# Overview.net
KiCad netlist of a schematic drawn in Altium Designer
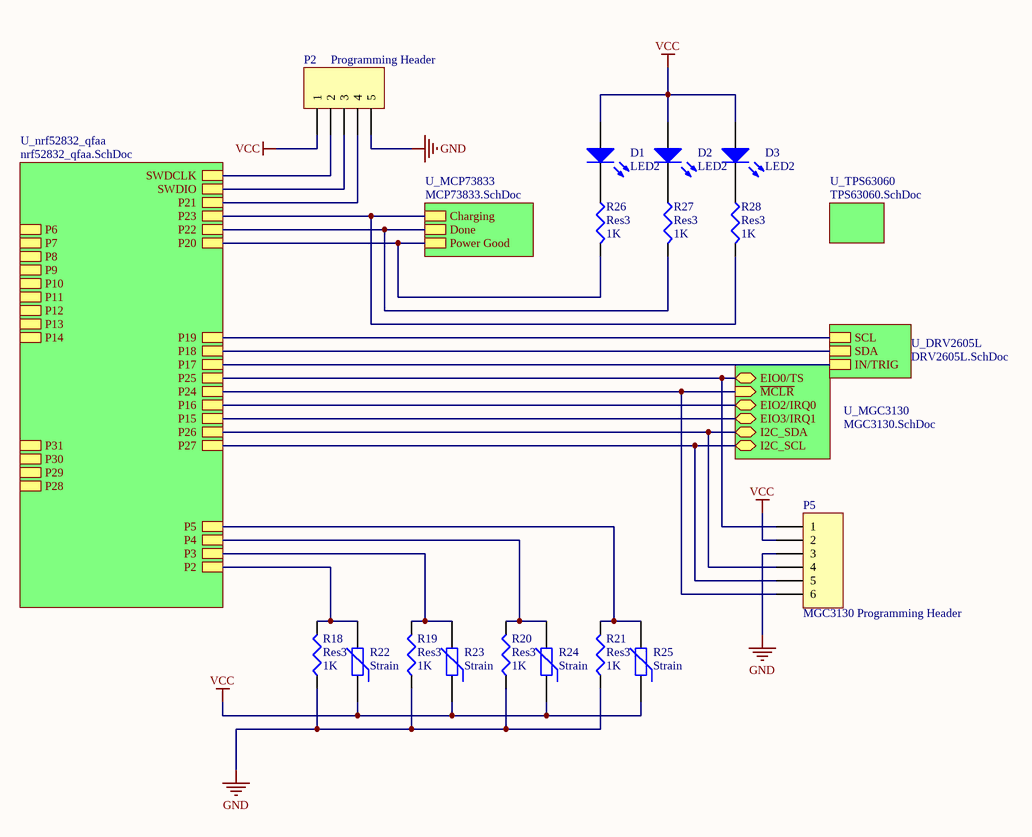
[diagram p0: Overview.SchDoc]

(export (version "E")
  (design (tool "Eeschema 10.0.6"))
  (components
    (comp (ref "D1")
      (value "LED2")
      (footprint "3.2X1.6X1.1")
      (description "Typical RED, GREEN, YELLOW, AMBER GaAs LED")
      (fields (field (name "PUBLISHER") "Altium Limited"))
      (libsource (lib "Miscellaneous Devices") (part "LED2"))
    )
    (comp (ref "D2")
      (value "LED2")
      (footprint "3.2X1.6X1.1")
      (description "Typical RED, GREEN, YELLOW, AMBER GaAs LED")
      (fields (field (name "PUBLISHER") "Altium Limited"))
      (libsource (lib "Miscellaneous Devices") (part "LED2"))
    )
    (comp (ref "D3")
      (value "LED2")
      (footprint "3.2X1.6X1.1")
      (description "Typical RED, GREEN, YELLOW, AMBER GaAs LED")
      (fields (field (name "PUBLISHER") "Altium Limited"))
      (libsource (lib "Miscellaneous Devices") (part "LED2"))
    )
    (comp (ref "P2")
      (value "Programming Header")
      (footprint "HDR1X5")
      (description "Header, 5-Pin")
      (fields (field (name "PUBLISHER") "Altium Limited"))
      (libsource (lib "Miscellaneous Connectors") (part "Header 5"))
    )
    (comp (ref "P5")
      (value "MGC3130 Programming Header")
      (footprint "HDR1X6")
      (description "Header, 6-Pin")
      (fields (field (name "PUBLISHER") "Altium Limited"))
      (libsource (lib "Miscellaneous Connectors") (part "Header 6"))
    )
    (comp (ref "R18")
      (value "Res3")
      (footprint "J1-0603")
      (description "Resistor")
      (fields (field (name "ALTIUM_VALUE") "1K") (field (name "PUBLISHER") "Altium Limited"))
      (libsource (lib "Miscellaneous Devices") (part "Res3"))
    )
    (comp (ref "R19")
      (value "Res3")
      (footprint "J1-0603")
      (description "Resistor")
      (fields (field (name "ALTIUM_VALUE") "1K") (field (name "PUBLISHER") "Altium Limited"))
      (libsource (lib "Miscellaneous Devices") (part "Res3"))
    )
    (comp (ref "R20")
      (value "Res3")
      (footprint "J1-0603")
      (description "Resistor")
      (fields (field (name "ALTIUM_VALUE") "1K") (field (name "PUBLISHER") "Altium Limited"))
      (libsource (lib "Miscellaneous Devices") (part "Res3"))
    )
    (comp (ref "R21")
      (value "Res3")
      (footprint "J1-0603")
      (description "Resistor")
      (fields (field (name "ALTIUM_VALUE") "1K") (field (name "PUBLISHER") "Altium Limited"))
      (libsource (lib "Miscellaneous Devices") (part "Res3"))
    )
    (comp (ref "R22")
      (value "Strain")
      (footprint "6-0805_N")
      (description "Varistor (Voltage-Sensitive Resistor)")
      (fields (field (name "PUBLISHER") "Altium Limited"))
      (libsource (lib "Miscellaneous Devices") (part "Res Varistor"))
    )
    (comp (ref "R23")
      (value "Strain")
      (footprint "6-0805_N")
      (description "Varistor (Voltage-Sensitive Resistor)")
      (fields (field (name "PUBLISHER") "Altium Limited"))
      (libsource (lib "Miscellaneous Devices") (part "Res Varistor"))
    )
    (comp (ref "R24")
      (value "Strain")
      (footprint "6-0805_N")
      (description "Varistor (Voltage-Sensitive Resistor)")
      (fields (field (name "PUBLISHER") "Altium Limited"))
      (libsource (lib "Miscellaneous Devices") (part "Res Varistor"))
    )
    (comp (ref "R25")
      (value "Strain")
      (footprint "6-0805_N")
      (description "Varistor (Voltage-Sensitive Resistor)")
      (fields (field (name "PUBLISHER") "Altium Limited"))
      (libsource (lib "Miscellaneous Devices") (part "Res Varistor"))
    )
    (comp (ref "R26")
      (value "Res3")
      (footprint "J1-0603")
      (description "Resistor")
      (fields (field (name "ALTIUM_VALUE") "1K") (field (name "PUBLISHER") "Altium Limited"))
      (libsource (lib "Miscellaneous Devices") (part "Res3"))
    )
    (comp (ref "R27")
      (value "Res3")
      (footprint "J1-0603")
      (description "Resistor")
      (fields (field (name "ALTIUM_VALUE") "1K") (field (name "PUBLISHER") "Altium Limited"))
      (libsource (lib "Miscellaneous Devices") (part "Res3"))
    )
    (comp (ref "R28")
      (value "Res3")
      (footprint "J1-0603")
      (description "Resistor")
      (fields (field (name "ALTIUM_VALUE") "1K") (field (name "PUBLISHER") "Altium Limited"))
      (libsource (lib "Miscellaneous Devices") (part "Res3"))
    )
  )
  (nets
    (net (code "1") (name "/Charging") (class "Default")
      (node (ref "R28") (pin "2") (pinfunction "2_2") (pintype "passive"))
    )
    (net (code "2") (name "/Done") (class "Default")
      (node (ref "R27") (pin "2") (pinfunction "2_2") (pintype "passive"))
    )
    (net (code "3") (name "/EIO0{slash}TS") (class "Default")
      (node (ref "P5") (pin "1") (pinfunction "1_1") (pintype "passive"))
    )
    (net (code "6") (name "/I2C_SCL") (class "Default")
      (node (ref "P5") (pin "5") (pinfunction "5_5") (pintype "passive"))
    )
    (net (code "7") (name "/I2C_SDA") (class "Default")
      (node (ref "P5") (pin "4") (pinfunction "4_4") (pintype "passive"))
    )
    (net (code "9") (name "/P2") (class "Default")
      (node (ref "R18") (pin "2") (pinfunction "2_2") (pintype "passive"))
      (node (ref "R22") (pin "2") (pinfunction "2_2") (pintype "passive"))
    )
    (net (code "10") (name "/P3") (class "Default")
      (node (ref "R19") (pin "2") (pinfunction "2_2") (pintype "passive"))
      (node (ref "R23") (pin "2") (pinfunction "2_2") (pintype "passive"))
    )
    (net (code "11") (name "/P4") (class "Default")
      (node (ref "R20") (pin "2") (pinfunction "2_2") (pintype "passive"))
      (node (ref "R24") (pin "2") (pinfunction "2_2") (pintype "passive"))
    )
    (net (code "12") (name "/P5") (class "Default")
      (node (ref "R21") (pin "2") (pinfunction "2_2") (pintype "passive"))
      (node (ref "R25") (pin "2") (pinfunction "2_2") (pintype "passive"))
    )
    (net (code "24") (name "/P20") (class "Default")
      (node (ref "R26") (pin "2") (pinfunction "2_2") (pintype "passive"))
    )
    (net (code "25") (name "/P21") (class "Default")
      (node (ref "P2") (pin "4") (pinfunction "4_4") (pintype "passive"))
    )
    (net (code "26") (name "/P24") (class "Default")
      (node (ref "P5") (pin "6") (pinfunction "6_6") (pintype "passive"))
    )
    (net (code "31") (name "/SWDCLK") (class "Default")
      (node (ref "P2") (pin "2") (pinfunction "2_2") (pintype "passive"))
    )
    (net (code "32") (name "/SWDIO") (class "Default")
      (node (ref "P2") (pin "3") (pinfunction "3_3") (pintype "passive"))
    )
    (net (code "33") (name "GND") (class "Default")
      (node (ref "P2") (pin "5") (pinfunction "5_5") (pintype "passive"))
      (node (ref "P5") (pin "3") (pinfunction "3_3") (pintype "passive"))
      (node (ref "R18") (pin "1") (pinfunction "1_1") (pintype "passive"))
      (node (ref "R19") (pin "1") (pinfunction "1_1") (pintype "passive"))
      (node (ref "R20") (pin "1") (pinfunction "1_1") (pintype "passive"))
      (node (ref "R21") (pin "1") (pinfunction "1_1") (pintype "passive"))
    )
    (net (code "34") (name "Net-(D1-K)") (class "Default")
      (node (ref "D1") (pin "2") (pinfunction "K_2") (pintype "passive"))
      (node (ref "R26") (pin "1") (pinfunction "1_1") (pintype "passive"))
    )
    (net (code "35") (name "Net-(D2-K)") (class "Default")
      (node (ref "D2") (pin "2") (pinfunction "K_2") (pintype "passive"))
      (node (ref "R27") (pin "1") (pinfunction "1_1") (pintype "passive"))
    )
    (net (code "36") (name "Net-(D3-K)") (class "Default")
      (node (ref "D3") (pin "2") (pinfunction "K_2") (pintype "passive"))
      (node (ref "R28") (pin "1") (pinfunction "1_1") (pintype "passive"))
    )
    (net (code "37") (name "VCC") (class "Default")
      (node (ref "D1") (pin "1") (pinfunction "A_1") (pintype "passive"))
      (node (ref "D2") (pin "1") (pinfunction "A_1") (pintype "passive"))
      (node (ref "D3") (pin "1") (pinfunction "A_1") (pintype "passive"))
      (node (ref "P2") (pin "1") (pinfunction "1_1") (pintype "passive"))
      (node (ref "P5") (pin "2") (pinfunction "2_2") (pintype "passive"))
      (node (ref "R22") (pin "1") (pinfunction "1_1") (pintype "passive"))
      (node (ref "R23") (pin "1") (pinfunction "1_1") (pintype "passive"))
      (node (ref "R24") (pin "1") (pinfunction "1_1") (pintype "passive"))
      (node (ref "R25") (pin "1") (pinfunction "1_1") (pintype "passive"))
    )
  )
)
